# Microcontroller_Microchip_dsPIC33EP256MU.net
KiCad netlist of a schematic drawn in EAGLE
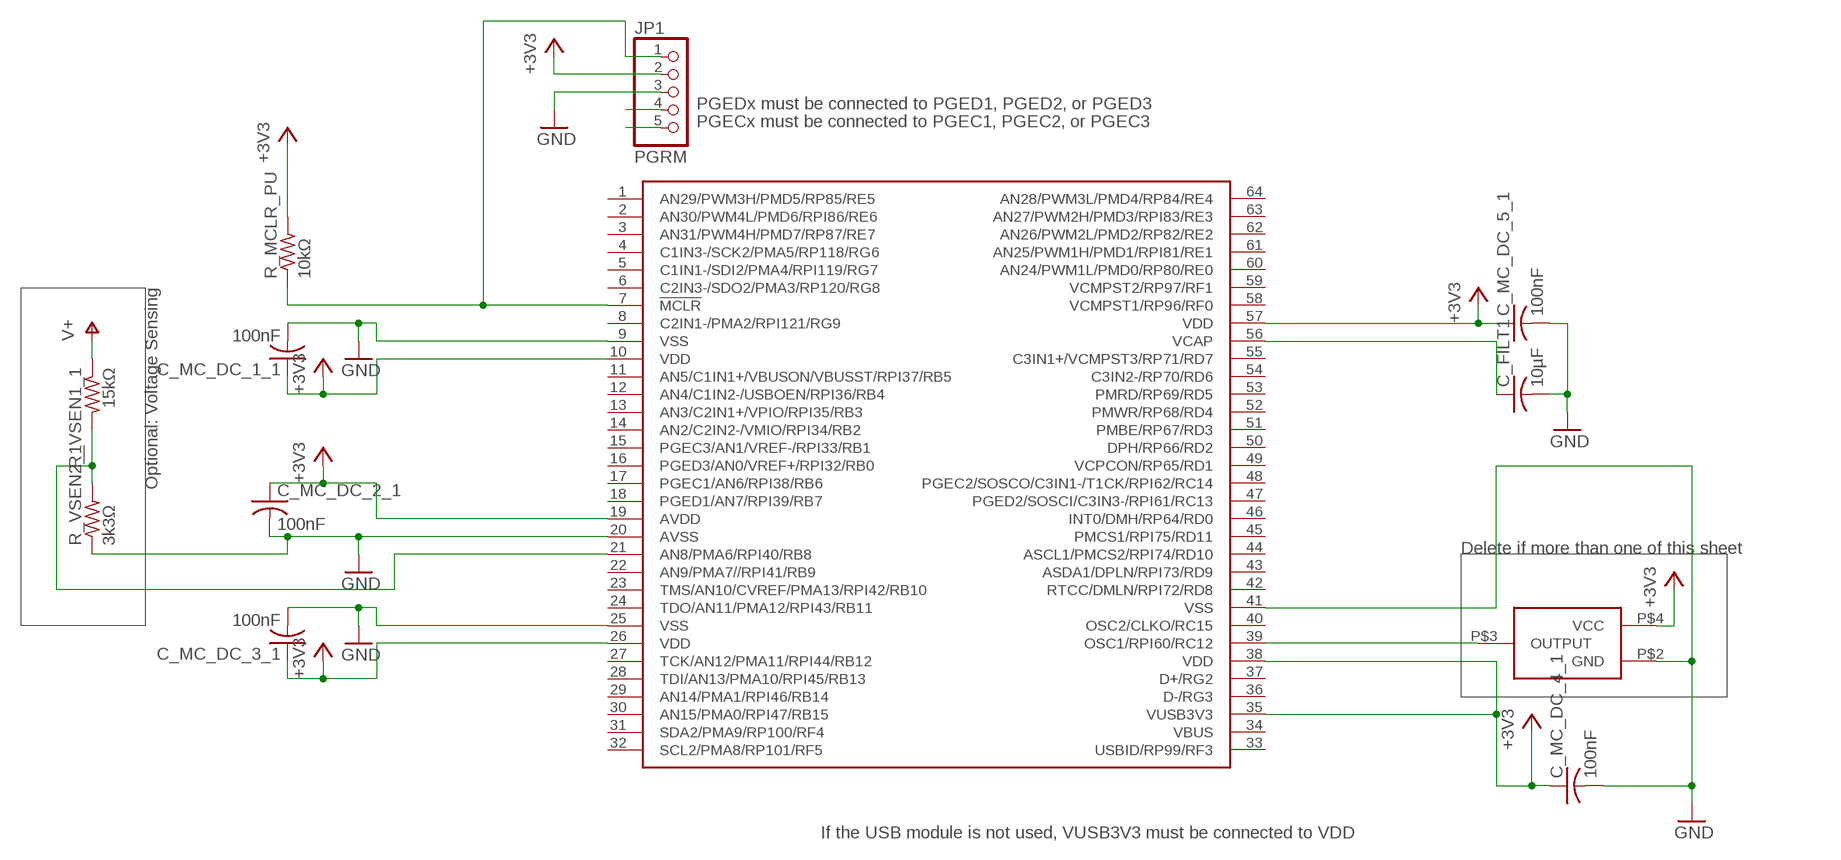
[diagram p0: schematic, sheet 1]

(export (version "E")
  (design (tool "Eeschema 10.0.6"))
  (components
    (comp (ref "C_FILT1")
      (value "10µF")
      (footprint "eagle-import:C0805")
      (libsource (lib "eagle-import") (part "C-USC0805"))
    )
    (comp (ref "C_MC_DC_1_1")
      (value "100nF")
      (footprint "eagle-import:C0603")
      (libsource (lib "eagle-import") (part "C-USC0603"))
    )
    (comp (ref "C_MC_DC_2_1")
      (value "100nF")
      (footprint "eagle-import:C0603")
      (libsource (lib "eagle-import") (part "C-USC0603"))
    )
    (comp (ref "C_MC_DC_3_1")
      (value "100nF")
      (footprint "eagle-import:C0603")
      (libsource (lib "eagle-import") (part "C-USC0603"))
    )
    (comp (ref "C_MC_DC_4_1")
      (value "100nF")
      (footprint "eagle-import:C0603")
      (libsource (lib "eagle-import") (part "C-USC0603"))
    )
    (comp (ref "C_MC_DC_5_1")
      (value "100nF")
      (footprint "eagle-import:C0603")
      (libsource (lib "eagle-import") (part "C-USC0603"))
    )
    (comp (ref "JP1")
      (value "PGRM")
      (footprint "eagle-import:1X05M")
      (libsource (lib "eagle-import") (part "PINHD-1X05_2.00"))
    )
    (comp (ref "MC1")
      (value "DSPIC33EP256MU806-I/PT")
      (footprint "eagle-import:S-PQFP-G64")
      (libsource (lib "eagle-import") (part "DSPIC33EP256MU806-I/PT"))
    )
    (comp (ref "OSC1")
      (value "FOX924B")
      (footprint "eagle-import:4-SMD_5X3.2")
      (libsource (lib "eagle-import") (part "FOX924B"))
    )
    (comp (ref "R_MCLR_PU")
      (value "10kΩ")
      (footprint "eagle-import:R0603")
      (libsource (lib "eagle-import") (part "R-US_R0603"))
    )
    (comp (ref "R_VSEN1_1")
      (value "15kΩ")
      (footprint "eagle-import:R0603")
      (libsource (lib "eagle-import") (part "R-US_R0603"))
    )
    (comp (ref "R_VSEN2_1")
      (value "3k3Ω")
      (footprint "eagle-import:R0603")
      (libsource (lib "eagle-import") (part "R-US_R0603"))
    )
  )
  (nets
    (net (code "1") (name "+3V3") (class "Default")
      (node (ref "C_MC_DC_1_1") (pin "1") (pinfunction "1_1") (pintype "passive"))
      (node (ref "C_MC_DC_2_1") (pin "1") (pinfunction "1_1") (pintype "passive"))
      (node (ref "C_MC_DC_3_1") (pin "1") (pinfunction "1_1") (pintype "passive"))
      (node (ref "C_MC_DC_4_1") (pin "1") (pinfunction "1_1") (pintype "passive"))
      (node (ref "C_MC_DC_5_1") (pin "1") (pinfunction "1_1") (pintype "passive"))
      (node (ref "JP1") (pin "2") (pinfunction "2_2") (pintype "passive"))
      (node (ref "MC1") (pin "10") (pinfunction "VDD_10") (pintype "power_in"))
      (node (ref "MC1") (pin "19") (pinfunction "AVDD_19") (pintype "power_in"))
      (node (ref "MC1") (pin "26") (pinfunction "VDD_26") (pintype "power_in"))
      (node (ref "MC1") (pin "35") (pinfunction "VUSB3V3_35") (pintype "bidirectional"))
      (node (ref "MC1") (pin "38") (pinfunction "VDD_38") (pintype "power_in"))
      (node (ref "MC1") (pin "57") (pinfunction "VDD_57") (pintype "power_in"))
      (node (ref "OSC1") (pin "P$4") (pinfunction "VCC_P$4") (pintype "bidirectional"))
      (node (ref "R_MCLR_PU") (pin "2") (pinfunction "2_2") (pintype "passive"))
    )
    (net (code "2") (name "GND") (class "Default")
      (node (ref "C_FILT1") (pin "2") (pinfunction "2_2") (pintype "passive"))
      (node (ref "C_MC_DC_1_1") (pin "2") (pinfunction "2_2") (pintype "passive"))
      (node (ref "C_MC_DC_2_1") (pin "2") (pinfunction "2_2") (pintype "passive"))
      (node (ref "C_MC_DC_3_1") (pin "2") (pinfunction "2_2") (pintype "passive"))
      (node (ref "C_MC_DC_4_1") (pin "2") (pinfunction "2_2") (pintype "passive"))
      (node (ref "C_MC_DC_5_1") (pin "2") (pinfunction "2_2") (pintype "passive"))
      (node (ref "JP1") (pin "3") (pinfunction "3_3") (pintype "passive"))
      (node (ref "MC1") (pin "20") (pinfunction "AVSS_20") (pintype "power_in"))
      (node (ref "MC1") (pin "25") (pinfunction "VSS_25") (pintype "power_in"))
      (node (ref "MC1") (pin "41") (pinfunction "VSS_41") (pintype "power_in"))
      (node (ref "MC1") (pin "9") (pinfunction "VSS_9") (pintype "power_in"))
      (node (ref "OSC1") (pin "P$2") (pinfunction "GND_P$2") (pintype "bidirectional"))
      (node (ref "R_VSEN2_1") (pin "1") (pinfunction "1_1") (pintype "passive"))
    )
    (net (code "3") (name "Net-(MC1-AN8{slash}PMA6{slash}RPI40{slash}RB8)") (class "Default")
      (node (ref "MC1") (pin "21") (pinfunction "AN8/PMA6/RPI40/RB8_21") (pintype "bidirectional"))
      (node (ref "R_VSEN1_1") (pin "2") (pinfunction "2_2") (pintype "passive"))
      (node (ref "R_VSEN2_1") (pin "2") (pinfunction "2_2") (pintype "passive"))
    )
    (net (code "4") (name "Net-(MC1-OSC1{slash}RPI60{slash}RC12)") (class "Default")
      (node (ref "MC1") (pin "39") (pinfunction "OSC1/RPI60/RC12_39") (pintype "bidirectional"))
      (node (ref "OSC1") (pin "P$3") (pinfunction "OUTPUT_P$3") (pintype "bidirectional"))
    )
    (net (code "5") (name "Net-(MC1-VCAP)") (class "Default")
      (node (ref "C_FILT1") (pin "1") (pinfunction "1_1") (pintype "passive"))
      (node (ref "MC1") (pin "56") (pinfunction "VCAP_56") (pintype "power_in"))
    )
    (net (code "6") (name "Net-(MC1-~{MCLR})") (class "Default")
      (node (ref "JP1") (pin "1") (pinfunction "1_1") (pintype "passive"))
      (node (ref "MC1") (pin "7") (pinfunction "~{MCLR}_7") (pintype "input"))
      (node (ref "R_MCLR_PU") (pin "1") (pinfunction "1_1") (pintype "passive"))
    )
    (net (code "7") (name "V+") (class "Default")
      (node (ref "R_VSEN1_1") (pin "1") (pinfunction "1_1") (pintype "passive"))
    )
    (net (code "8") (name "unconnected-(JP1-Pad4)") (class "Default")
      (node (ref "JP1") (pin "4") (pinfunction "4_4") (pintype "passive"))
    )
    (net (code "9") (name "unconnected-(JP1-Pad5)") (class "Default")
      (node (ref "JP1") (pin "5") (pinfunction "5_5") (pintype "passive"))
    )
    (net (code "10") (name "unconnected-(MC1-AN2{slash}C2IN2-{slash}VMIO{slash}RPI34{slash}RB2-Pad14)") (class "Default")
      (node (ref "MC1") (pin "14") (pinfunction "AN2/C2IN2-/VMIO/RPI34/RB2_14") (pintype "bidirectional"))
    )
    (net (code "11") (name "unconnected-(MC1-AN3{slash}C2IN1+{slash}VPIO{slash}RPI35{slash}RB3-Pad13)") (class "Default")
      (node (ref "MC1") (pin "13") (pinfunction "AN3/C2IN1+/VPIO/RPI35/RB3_13") (pintype "bidirectional"))
    )
    (net (code "12") (name "unconnected-(MC1-AN4{slash}C1IN2-{slash}USBOEN{slash}RPI36{slash}RB4-Pad12)") (class "Default")
      (node (ref "MC1") (pin "12") (pinfunction "AN4/C1IN2-/USBOEN/RPI36/RB4_12") (pintype "bidirectional"))
    )
    (net (code "13") (name "unconnected-(MC1-AN5{slash}C1IN1+{slash}VBUSON{slash}VBUSST{slash}RPI37{slash}RB5-Pad11)") (class "Default")
      (node (ref "MC1") (pin "11") (pinfunction "AN5/C1IN1+/VBUSON/VBUSST/RPI37/RB5_11") (pintype "bidirectional"))
    )
    (net (code "14") (name "unconnected-(MC1-AN9{slash}PMA7{slash}{slash}RPI41{slash}RB9-Pad22)") (class "Default")
      (node (ref "MC1") (pin "22") (pinfunction "AN9/PMA7//RPI41/RB9_22") (pintype "bidirectional"))
    )
    (net (code "15") (name "unconnected-(MC1-AN14{slash}PMA1{slash}RPI46{slash}RB14-Pad29)") (class "Default")
      (node (ref "MC1") (pin "29") (pinfunction "AN14/PMA1/RPI46/RB14_29") (pintype "bidirectional"))
    )
    (net (code "16") (name "unconnected-(MC1-AN15{slash}PMA0{slash}RPI47{slash}RB15-Pad30)") (class "Default")
      (node (ref "MC1") (pin "30") (pinfunction "AN15/PMA0/RPI47/RB15_30") (pintype "bidirectional"))
    )
    (net (code "17") (name "unconnected-(MC1-AN24{slash}PWM1L{slash}PMD0{slash}RP80{slash}RE0-Pad60)") (class "Default")
      (node (ref "MC1") (pin "60") (pinfunction "AN24/PWM1L/PMD0/RP80/RE0_60") (pintype "bidirectional"))
    )
    (net (code "18") (name "unconnected-(MC1-AN25{slash}PWM1H{slash}PMD1{slash}RPI81{slash}RE1-Pad61)") (class "Default")
      (node (ref "MC1") (pin "61") (pinfunction "AN25/PWM1H/PMD1/RPI81/RE1_61") (pintype "bidirectional"))
    )
    (net (code "19") (name "unconnected-(MC1-AN26{slash}PWM2L{slash}PMD2{slash}RP82{slash}RE2-Pad62)") (class "Default")
      (node (ref "MC1") (pin "62") (pinfunction "AN26/PWM2L/PMD2/RP82/RE2_62") (pintype "bidirectional"))
    )
    (net (code "20") (name "unconnected-(MC1-AN27{slash}PWM2H{slash}PMD3{slash}RPI83{slash}RE3-Pad63)") (class "Default")
      (node (ref "MC1") (pin "63") (pinfunction "AN27/PWM2H/PMD3/RPI83/RE3_63") (pintype "bidirectional"))
    )
    (net (code "21") (name "unconnected-(MC1-AN28{slash}PWM3L{slash}PMD4{slash}RP84{slash}RE4-Pad64)") (class "Default")
      (node (ref "MC1") (pin "64") (pinfunction "AN28/PWM3L/PMD4/RP84/RE4_64") (pintype "bidirectional"))
    )
    (net (code "22") (name "unconnected-(MC1-AN29{slash}PWM3H{slash}PMD5{slash}RP85{slash}RE5-Pad1)") (class "Default")
      (node (ref "MC1") (pin "1") (pinfunction "AN29/PWM3H/PMD5/RP85/RE5_1") (pintype "bidirectional"))
    )
    (net (code "23") (name "unconnected-(MC1-AN30{slash}PWM4L{slash}PMD6{slash}RPI86{slash}RE6-Pad2)") (class "Default")
      (node (ref "MC1") (pin "2") (pinfunction "AN30/PWM4L/PMD6/RPI86/RE6_2") (pintype "bidirectional"))
    )
    (net (code "24") (name "unconnected-(MC1-AN31{slash}PWM4H{slash}PMD7{slash}RP87{slash}RE7-Pad3)") (class "Default")
      (node (ref "MC1") (pin "3") (pinfunction "AN31/PWM4H/PMD7/RP87/RE7_3") (pintype "bidirectional"))
    )
    (net (code "25") (name "unconnected-(MC1-ASCL1{slash}PMCS2{slash}RPI74{slash}RD10-Pad44)") (class "Default")
      (node (ref "MC1") (pin "44") (pinfunction "ASCL1/PMCS2/RPI74/RD10_44") (pintype "bidirectional"))
    )
    (net (code "26") (name "unconnected-(MC1-ASDA1{slash}DPLN{slash}RPI73{slash}RD9-Pad43)") (class "Default")
      (node (ref "MC1") (pin "43") (pinfunction "ASDA1/DPLN/RPI73/RD9_43") (pintype "bidirectional"))
    )
    (net (code "27") (name "unconnected-(MC1-C1IN1-{slash}SDI2{slash}PMA4{slash}RPI119{slash}RG7-Pad5)") (class "Default")
      (node (ref "MC1") (pin "5") (pinfunction "C1IN1-/SDI2/PMA4/RPI119/RG7_5") (pintype "bidirectional"))
    )
    (net (code "28") (name "unconnected-(MC1-C1IN3-{slash}SCK2{slash}PMA5{slash}RP118{slash}RG6-Pad4)") (class "Default")
      (node (ref "MC1") (pin "4") (pinfunction "C1IN3-/SCK2/PMA5/RP118/RG6_4") (pintype "bidirectional"))
    )
    (net (code "29") (name "unconnected-(MC1-C2IN1-{slash}PMA2{slash}RPI121{slash}RG9-Pad8)") (class "Default")
      (node (ref "MC1") (pin "8") (pinfunction "C2IN1-/PMA2/RPI121/RG9_8") (pintype "bidirectional"))
    )
    (net (code "30") (name "unconnected-(MC1-C2IN3-{slash}SDO2{slash}PMA3{slash}RP120{slash}RG8-Pad6)") (class "Default")
      (node (ref "MC1") (pin "6") (pinfunction "C2IN3-/SDO2/PMA3/RP120/RG8_6") (pintype "bidirectional"))
    )
    (net (code "31") (name "unconnected-(MC1-C3IN1+{slash}VCMPST3{slash}RP71{slash}RD7-Pad55)") (class "Default")
      (node (ref "MC1") (pin "55") (pinfunction "C3IN1+/VCMPST3/RP71/RD7_55") (pintype "bidirectional"))
    )
    (net (code "32") (name "unconnected-(MC1-C3IN2-{slash}RP70{slash}RD6-Pad54)") (class "Default")
      (node (ref "MC1") (pin "54") (pinfunction "C3IN2-/RP70/RD6_54") (pintype "bidirectional"))
    )
    (net (code "33") (name "unconnected-(MC1-D+{slash}RG2-Pad37)") (class "Default")
      (node (ref "MC1") (pin "37") (pinfunction "D+/RG2_37") (pintype "bidirectional"))
    )
    (net (code "34") (name "unconnected-(MC1-D-{slash}RG3-Pad36)") (class "Default")
      (node (ref "MC1") (pin "36") (pinfunction "D-/RG3_36") (pintype "bidirectional"))
    )
    (net (code "35") (name "unconnected-(MC1-DPH{slash}RP66{slash}RD2-Pad50)") (class "Default")
      (node (ref "MC1") (pin "50") (pinfunction "DPH/RP66/RD2_50") (pintype "bidirectional"))
    )
    (net (code "36") (name "unconnected-(MC1-INT0{slash}DMH{slash}RP64{slash}RD0-Pad46)") (class "Default")
      (node (ref "MC1") (pin "46") (pinfunction "INT0/DMH/RP64/RD0_46") (pintype "bidirectional"))
    )
    (net (code "37") (name "unconnected-(MC1-OSC2{slash}CLKO{slash}RC15-Pad40)") (class "Default")
      (node (ref "MC1") (pin "40") (pinfunction "OSC2/CLKO/RC15_40") (pintype "bidirectional"))
    )
    (net (code "38") (name "unconnected-(MC1-PGEC1{slash}AN6{slash}RPI38{slash}RB6-Pad17)") (class "Default")
      (node (ref "MC1") (pin "17") (pinfunction "PGEC1/AN6/RPI38/RB6_17") (pintype "bidirectional"))
    )
    (net (code "39") (name "unconnected-(MC1-PGEC2{slash}SOSCO{slash}C3IN1-{slash}T1CK{slash}RPI62{slash}RC14-Pad48)") (class "Default")
      (node (ref "MC1") (pin "48") (pinfunction "PGEC2/SOSCO/C3IN1-/T1CK/RPI62/RC14_48") (pintype "bidirectional"))
    )
    (net (code "40") (name "unconnected-(MC1-PGEC3{slash}AN1{slash}VREF-{slash}RPI33{slash}RB1-Pad15)") (class "Default")
      (node (ref "MC1") (pin "15") (pinfunction "PGEC3/AN1/VREF-/RPI33/RB1_15") (pintype "bidirectional"))
    )
    (net (code "41") (name "unconnected-(MC1-PGED1{slash}AN7{slash}RPI39{slash}RB7-Pad18)") (class "Default")
      (node (ref "MC1") (pin "18") (pinfunction "PGED1/AN7/RPI39/RB7_18") (pintype "bidirectional"))
    )
    (net (code "42") (name "unconnected-(MC1-PGED2{slash}SOSCI{slash}C3IN3-{slash}RPI61{slash}RC13-Pad47)") (class "Default")
      (node (ref "MC1") (pin "47") (pinfunction "PGED2/SOSCI/C3IN3-/RPI61/RC13_47") (pintype "bidirectional"))
    )
    (net (code "43") (name "unconnected-(MC1-PGED3{slash}AN0{slash}VREF+{slash}RPI32{slash}RB0-Pad16)") (class "Default")
      (node (ref "MC1") (pin "16") (pinfunction "PGED3/AN0/VREF+/RPI32/RB0_16") (pintype "bidirectional"))
    )
    (net (code "44") (name "unconnected-(MC1-PMBE{slash}RP67{slash}RD3-Pad51)") (class "Default")
      (node (ref "MC1") (pin "51") (pinfunction "PMBE/RP67/RD3_51") (pintype "bidirectional"))
    )
    (net (code "45") (name "unconnected-(MC1-PMCS1{slash}RPI75{slash}RD11-Pad45)") (class "Default")
      (node (ref "MC1") (pin "45") (pinfunction "PMCS1/RPI75/RD11_45") (pintype "bidirectional"))
    )
    (net (code "46") (name "unconnected-(MC1-PMRD{slash}RP69{slash}RD5-Pad53)") (class "Default")
      (node (ref "MC1") (pin "53") (pinfunction "PMRD/RP69/RD5_53") (pintype "bidirectional"))
    )
    (net (code "47") (name "unconnected-(MC1-PMWR{slash}RP68{slash}RD4-Pad52)") (class "Default")
      (node (ref "MC1") (pin "52") (pinfunction "PMWR/RP68/RD4_52") (pintype "bidirectional"))
    )
    (net (code "48") (name "unconnected-(MC1-RTCC{slash}DMLN{slash}RPI72{slash}RD8-Pad42)") (class "Default")
      (node (ref "MC1") (pin "42") (pinfunction "RTCC/DMLN/RPI72/RD8_42") (pintype "bidirectional"))
    )
    (net (code "49") (name "unconnected-(MC1-SCL2{slash}PMA8{slash}RP101{slash}RF5-Pad32)") (class "Default")
      (node (ref "MC1") (pin "32") (pinfunction "SCL2/PMA8/RP101/RF5_32") (pintype "bidirectional"))
    )
    (net (code "50") (name "unconnected-(MC1-SDA2{slash}PMA9{slash}RP100{slash}RF4-Pad31)") (class "Default")
      (node (ref "MC1") (pin "31") (pinfunction "SDA2/PMA9/RP100/RF4_31") (pintype "bidirectional"))
    )
    (net (code "51") (name "unconnected-(MC1-TCK{slash}AN12{slash}PMA11{slash}RPI44{slash}RB12-Pad27)") (class "Default")
      (node (ref "MC1") (pin "27") (pinfunction "TCK/AN12/PMA11/RPI44/RB12_27") (pintype "bidirectional"))
    )
    (net (code "52") (name "unconnected-(MC1-TDI{slash}AN13{slash}PMA10{slash}RPI45{slash}RB13-Pad28)") (class "Default")
      (node (ref "MC1") (pin "28") (pinfunction "TDI/AN13/PMA10/RPI45/RB13_28") (pintype "bidirectional"))
    )
    (net (code "53") (name "unconnected-(MC1-TDO{slash}AN11{slash}PMA12{slash}RPI43{slash}RB11-Pad24)") (class "Default")
      (node (ref "MC1") (pin "24") (pinfunction "TDO/AN11/PMA12/RPI43/RB11_24") (pintype "bidirectional"))
    )
    (net (code "54") (name "unconnected-(MC1-TMS{slash}AN10{slash}CVREF{slash}PMA13{slash}RPI42{slash}RB10-Pad23)") (class "Default")
      (node (ref "MC1") (pin "23") (pinfunction "TMS/AN10/CVREF/PMA13/RPI42/RB10_23") (pintype "bidirectional"))
    )
    (net (code "55") (name "unconnected-(MC1-USBID{slash}RP99{slash}RF3-Pad33)") (class "Default")
      (node (ref "MC1") (pin "33") (pinfunction "USBID/RP99/RF3_33") (pintype "bidirectional"))
    )
    (net (code "56") (name "unconnected-(MC1-VBUS-Pad34)") (class "Default")
      (node (ref "MC1") (pin "34") (pinfunction "VBUS_34") (pintype "bidirectional"))
    )
    (net (code "57") (name "unconnected-(MC1-VCMPST1{slash}RP96{slash}RF0-Pad58)") (class "Default")
      (node (ref "MC1") (pin "58") (pinfunction "VCMPST1/RP96/RF0_58") (pintype "bidirectional"))
    )
    (net (code "58") (name "unconnected-(MC1-VCMPST2{slash}RP97{slash}RF1-Pad59)") (class "Default")
      (node (ref "MC1") (pin "59") (pinfunction "VCMPST2/RP97/RF1_59") (pintype "bidirectional"))
    )
    (net (code "59") (name "unconnected-(MC1-VCPCON{slash}RP65{slash}RD1-Pad49)") (class "Default")
      (node (ref "MC1") (pin "49") (pinfunction "VCPCON/RP65/RD1_49") (pintype "bidirectional"))
    )
  )
)
